# Detector2.net
KiCad netlist of a schematic drawn in Altium Designer
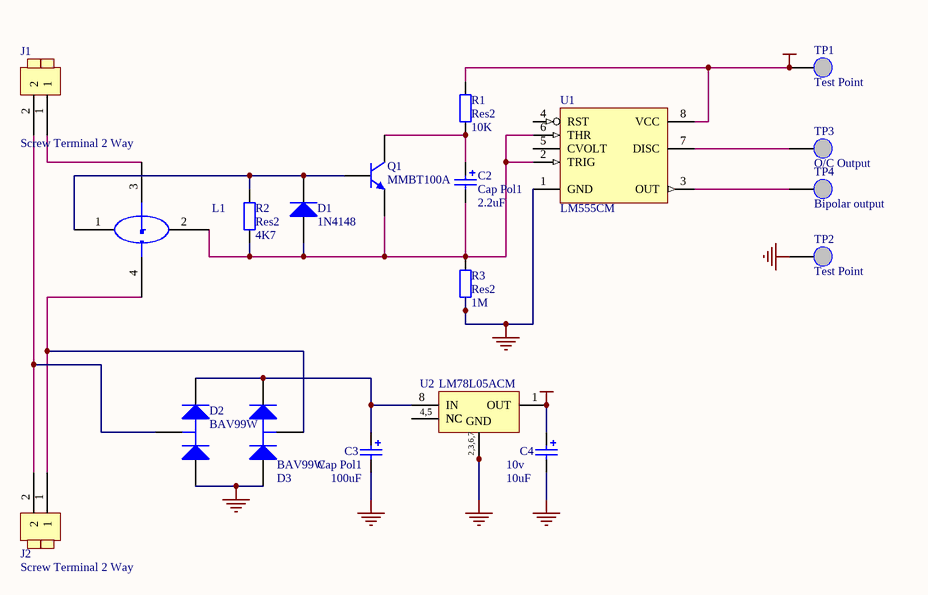
[diagram p0: Detector2.SchDoc]

(export (version "E")
  (design (tool "Eeschema 10.0.6"))
  (components
    (comp (ref "C2")
      (value "Cap Pol1")
      (footprint "CC3216-1206")
      (description "Polarized Capacitor (Radial)")
      (fields (field (name "ALTIUM_VALUE") "2.2uF") (field (name "PUBLISHER") "Altium Limited"))
      (libsource (lib "Miscellaneous Devices") (part "Cap Pol1"))
    )
    (comp (ref "C3")
      (value "Cap Pol1")
      (footprint "CC3216-1206")
      (description "Polarized Capacitor (Radial)")
      (fields (field (name "ALTIUM_VALUE") "100uF") (field (name "PUBLISHER") "Altium Limited"))
      (libsource (lib "Miscellaneous Devices") (part "Cap Pol1"))
    )
    (comp (ref "C4")
      (value "10v")
      (footprint "CC3216-1206")
      (description "Polarized Capacitor (Radial)")
      (fields (field (name "ALTIUM_VALUE") "10uF") (field (name "PUBLISHER") "Altium Limited"))
      (libsource (lib "Miscellaneous Devices") (part "Cap Pol1"))
    )
    (comp (ref "D1")
      (value "1N4148")
      (footprint "MELF-D3516-1406")
      (description "High Conductance Fast Diode")
      (fields (field (name "PUBLISHER") "Altium Limited"))
      (libsource (lib "Miscellaneous Devices") (part "Diode 1N4148"))
    )
    (comp (ref "D2")
      (value "BAV99W")
      (footprint "SOT-323")
      (description "Silicon Switching Diode Array for High-Speed Switching")
      (fields (field (name "PUBLISHER") "Altium Limited"))
      (libsource (lib "Infineon Discrete Diode") (part "BAV99W"))
    )
    (comp (ref "D3")
      (value "BAV99W")
      (footprint "SOT-323")
      (description "Silicon Switching Diode Array for High-Speed Switching")
      (fields (field (name "PUBLISHER") "Altium Limited"))
      (libsource (lib "Infineon Discrete Diode") (part "BAV99W"))
    )
    (comp (ref "J1")
      (value "Screw Terminal 2 Way")
      (footprint "Screw Terminal 2 way 0.2")
      (libsource (lib "Custom") (part "Screw Terminal 2 Way"))
    )
    (comp (ref "J2")
      (value "Screw Terminal 2 Way")
      (footprint "Screw Terminal 2 way 0.2")
      (libsource (lib "") (part "Screw Terminal 2 Way_1"))
    )
    (comp (ref "L1") (value "*") (footprint "VT-5") (libsource (lib "Custom") (part "VT-5")))
    (comp (ref "Q1")
      (value "MMBT100A")
      (footprint "SO-G3")
      (description "General Purpose Amplifier NPN Silicon")
      (fields (field (name "PUBLISHER") "Altium Limited"))
      (libsource (lib "Custom") (part "MMBT100A"))
    )
    (comp (ref "R1")
      (value "Res2")
      (footprint "CR2012-0805")
      (description "Resistor")
      (fields (field (name "ALTIUM_VALUE") "10K") (field (name "PUBLISHER") "Altium Limited"))
      (libsource (lib "Miscellaneous Devices") (part "Res2"))
    )
    (comp (ref "R2")
      (value "Res2")
      (footprint "CR2012-0805")
      (description "Resistor")
      (fields (field (name "ALTIUM_VALUE") "4K7") (field (name "PUBLISHER") "Altium Limited"))
      (libsource (lib "Miscellaneous Devices") (part "Res2"))
    )
    (comp (ref "R3")
      (value "Res2")
      (footprint "CR2012-0805")
      (description "Resistor")
      (fields (field (name "ALTIUM_VALUE") "1M") (field (name "PUBLISHER") "Altium Limited"))
      (libsource (lib "Miscellaneous Devices") (part "Res2"))
    )
    (comp (ref "TP1")
      (value "Test Point")
      (footprint "TestPoint")
      (libsource (lib "Custom") (part "TestPoint"))
    )
    (comp (ref "TP2")
      (value "Test Point")
      (footprint "TestPoint")
      (libsource (lib "Custom") (part "TestPoint"))
    )
    (comp (ref "TP3")
      (value "O/C Output")
      (footprint "TestPoint")
      (libsource (lib "Custom") (part "TestPoint"))
    )
    (comp (ref "TP4")
      (value "Bipolar output")
      (footprint "TestPoint")
      (libsource (lib "Custom") (part "TestPoint"))
    )
    (comp (ref "U1")
      (value "LM555CM")
      (footprint "M08A")
      (description "Timer")
      (fields (field (name "PUBLISHER") "Altium Limited"))
      (libsource (lib "NSC Analog Timer Circuit") (part "LM555CM"))
    )
    (comp (ref "U2")
      (value "LM78L05ACM")
      (footprint "M08A")
      (description "3-Terminal Positive Regulator")
      (fields (field (name "PUBLISHER") "Altium Limited"))
      (libsource (lib "NSC Power Mgt Voltage Regulator") (part "LM78L05ACM"))
    )
  )
  (nets
    (net (code "1") (name "GND") (class "Default")
      (node (ref "C3") (pin "2") (pinfunction "2_2") (pintype "passive"))
      (node (ref "C4") (pin "2") (pinfunction "2_2") (pintype "passive"))
      (node (ref "D2") (pin "1") (pinfunction "A_1") (pintype "passive"))
      (node (ref "D3") (pin "1") (pinfunction "A_1") (pintype "passive"))
      (node (ref "R3") (pin "1") (pinfunction "1_1") (pintype "passive"))
      (node (ref "TP2") (pin "1") (pintype "passive"))
      (node (ref "U1") (pin "1") (pinfunction "GND_1") (pintype "power_in"))
      (node (ref "U2") (pin "2") (pinfunction "GND_2") (pintype "power_in"))
      (node (ref "U2") (pin "3") (pinfunction "GND_3") (pintype "power_in"))
      (node (ref "U2") (pin "6") (pinfunction "GND_6") (pintype "power_in"))
      (node (ref "U2") (pin "7") (pinfunction "GND_7") (pintype "power_in"))
    )
    (net (code "2") (name "Net-(D1-A)") (class "Default")
      (node (ref "C2") (pin "2") (pinfunction "2_2") (pintype "passive"))
      (node (ref "D1") (pin "1") (pinfunction "A_1") (pintype "passive"))
      (node (ref "L1") (pin "2") (pinfunction "Coil_B_2") (pintype "passive"))
      (node (ref "Q1") (pin "2") (pinfunction "E_2") (pintype "passive"))
      (node (ref "R2") (pin "1") (pinfunction "1_1") (pintype "passive"))
      (node (ref "R3") (pin "2") (pinfunction "2_2") (pintype "passive"))
      (node (ref "U1") (pin "2") (pinfunction "TRIG_2") (pintype "input"))
      (node (ref "U1") (pin "6") (pinfunction "THR_6") (pintype "input"))
    )
    (net (code "3") (name "Net-(D1-K)") (class "Default")
      (node (ref "D1") (pin "2") (pinfunction "K_2") (pintype "passive"))
      (node (ref "L1") (pin "1") (pinfunction "CoilA_1") (pintype "passive"))
      (node (ref "Q1") (pin "1") (pinfunction "B_1") (pintype "passive"))
      (node (ref "R2") (pin "2") (pinfunction "2_2") (pintype "passive"))
    )
    (net (code "4") (name "Net-(D2-C)") (class "Default")
      (node (ref "D2") (pin "3") (pinfunction "C_3") (pintype "passive"))
      (node (ref "J1") (pin "2") (pinfunction "2_2") (pintype "passive"))
      (node (ref "J2") (pin "2") (pinfunction "2_2") (pintype "passive"))
    )
    (net (code "5") (name "Net-(D2-K)") (class "Default")
      (node (ref "C3") (pin "1") (pinfunction "1_1") (pintype "passive"))
      (node (ref "D2") (pin "2") (pinfunction "K_2") (pintype "passive"))
      (node (ref "D3") (pin "2") (pinfunction "K_2") (pintype "passive"))
      (node (ref "U2") (pin "8") (pinfunction "IN_8") (pintype "power_in"))
    )
    (net (code "6") (name "Net-(D3-C)") (class "Default")
      (node (ref "D3") (pin "3") (pinfunction "C_3") (pintype "passive"))
      (node (ref "J2") (pin "1") (pinfunction "1_1") (pintype "passive"))
      (node (ref "L1") (pin "4") (pinfunction "Wire_B_4") (pintype "passive"))
    )
    (net (code "7") (name "Net-(L1-Wire_A)") (class "Default")
      (node (ref "J1") (pin "1") (pinfunction "1_1") (pintype "passive"))
      (node (ref "L1") (pin "3") (pinfunction "Wire_A_3") (pintype "passive"))
    )
    (net (code "8") (name "Net-(Q1-C)") (class "Default")
      (node (ref "C2") (pin "1") (pinfunction "1_1") (pintype "passive"))
      (node (ref "Q1") (pin "3") (pinfunction "C_3") (pintype "passive"))
      (node (ref "R1") (pin "1") (pinfunction "1_1") (pintype "passive"))
    )
    (net (code "9") (name "Net-(U1-DISC)") (class "Default")
      (node (ref "TP3") (pin "1") (pintype "passive"))
      (node (ref "U1") (pin "7") (pinfunction "DISC_7") (pintype "open_collector"))
    )
    (net (code "10") (name "Net-(U1-OUT)") (class "Default")
      (node (ref "TP4") (pin "1") (pintype "passive"))
      (node (ref "U1") (pin "3") (pinfunction "OUT_3") (pintype "output"))
    )
    (net (code "11") (name "Net-(U2-NC-Pad4)") (class "Default")
      (node (ref "U2") (pin "4") (pinfunction "NC_4") (pintype "passive"))
      (node (ref "U2") (pin "5") (pinfunction "NC_5") (pintype "passive"))
    )
    (net (code "12") (name "VCC") (class "Default")
      (node (ref "C4") (pin "1") (pinfunction "1_1") (pintype "passive"))
      (node (ref "R1") (pin "2") (pinfunction "2_2") (pintype "passive"))
      (node (ref "TP1") (pin "1") (pintype "passive"))
      (node (ref "U1") (pin "8") (pinfunction "VCC_8") (pintype "power_in"))
      (node (ref "U2") (pin "1") (pinfunction "OUT_1") (pintype "power_in"))
    )
    (net (code "13") (name "unconnected-(U1-CVOLT-Pad5)") (class "Default")
      (node (ref "U1") (pin "5") (pinfunction "CVOLT_5") (pintype "passive"))
    )
    (net (code "14") (name "unconnected-(U1-RST-Pad4)") (class "Default")
      (node (ref "U1") (pin "4") (pinfunction "RST_4") (pintype "input"))
    )
  )
)
